# FE.net
KiCad netlist of a schematic drawn in Altium Designer
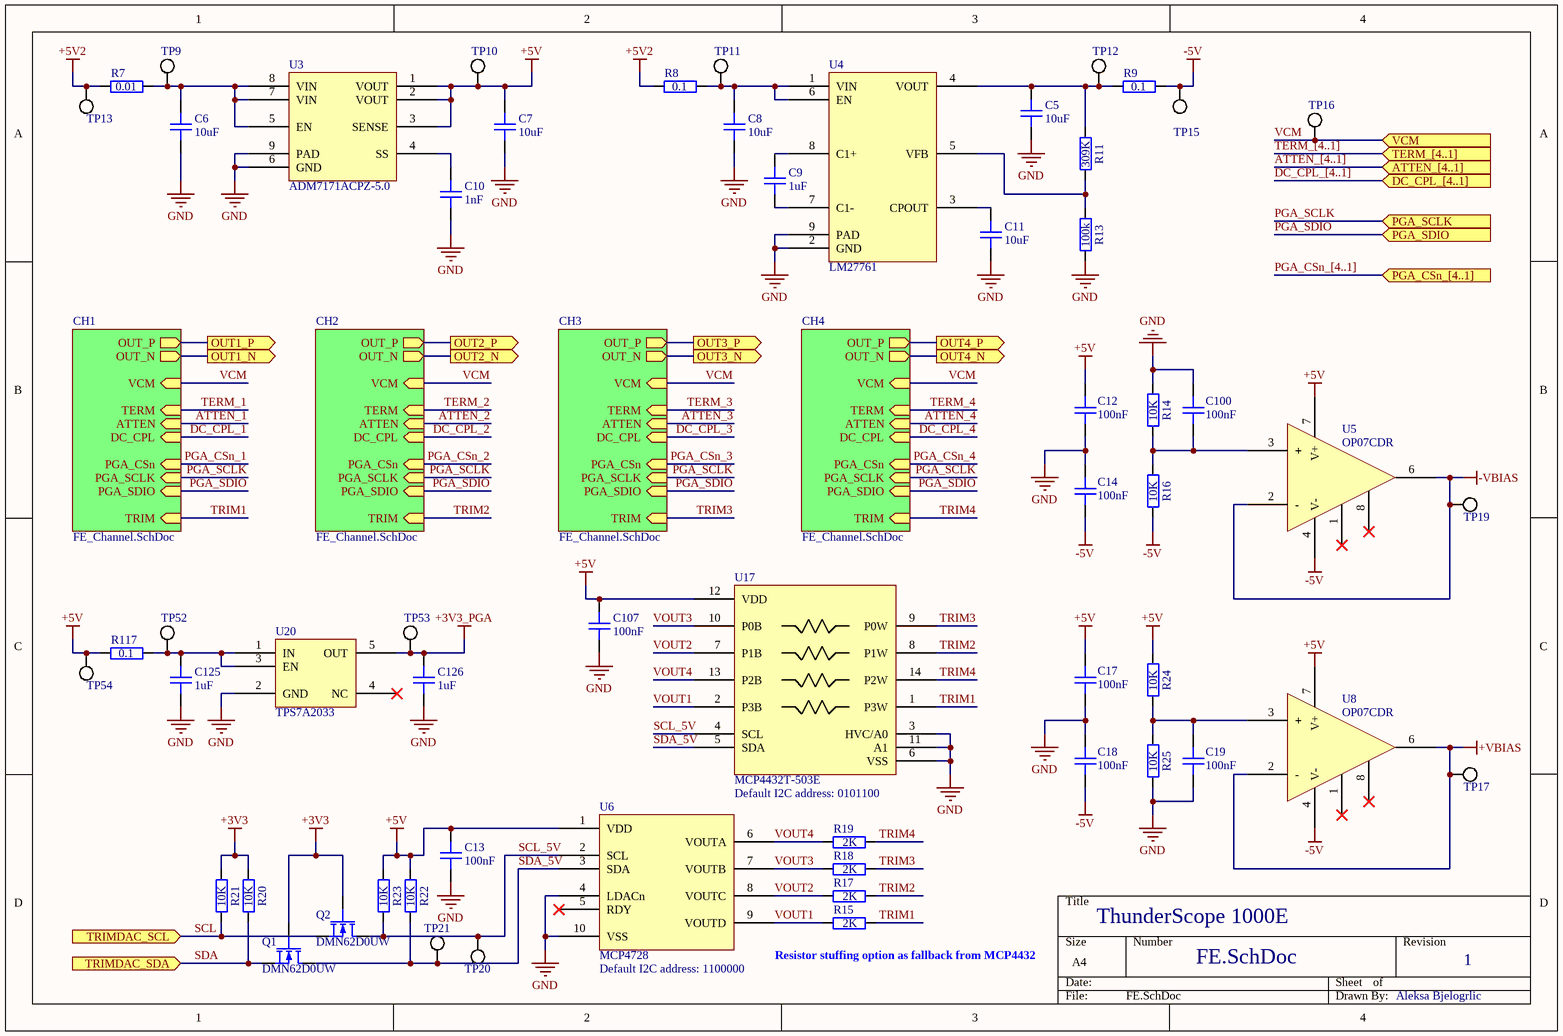
[diagram p0: FE.SchDoc]

(export (version "E")
  (design (tool "Eeschema 10.0.6"))
  (components
    (comp (ref "C5")
      (value "10uF")
      (footprint "GEN_C_0603")
      (libsource (lib "DSO") (part "CAP 10uF 10V X5R 0603"))
    )
    (comp (ref "C6")
      (value "10uF")
      (footprint "GEN_C_0603")
      (libsource (lib "DSO") (part "CAP 10uF 10V X5R 0603"))
    )
    (comp (ref "C7")
      (value "10uF")
      (footprint "GEN_C_0603")
      (libsource (lib "DSO") (part "CAP 10uF 10V X5R 0603"))
    )
    (comp (ref "C8")
      (value "10uF")
      (footprint "GEN_C_0603")
      (libsource (lib "DSO") (part "CAP 10uF 10V X5R 0603"))
    )
    (comp (ref "C9")
      (value "1uF")
      (footprint "GEN_C_0402")
      (libsource (lib "DSO") (part "CAP 1uF 25V X5R 0402"))
    )
    (comp (ref "C10")
      (value "1nF")
      (footprint "GEN_C_0402")
      (libsource (lib "DSO") (part "CAP 1nF 50V C0G 0402"))
    )
    (comp (ref "C11")
      (value "10uF")
      (footprint "GEN_C_0603")
      (libsource (lib "DSO") (part "CAP 10uF 10V X5R 0603"))
    )
    (comp (ref "C12")
      (value "100nF")
      (footprint "GEN_C_0402")
      (libsource (lib "DSO") (part "CAP 100nF 16V X7R 0402"))
    )
    (comp (ref "C13")
      (value "100nF")
      (footprint "GEN_C_0402")
      (libsource (lib "DSO") (part "CAP 100nF 16V X7R 0402"))
    )
    (comp (ref "C14")
      (value "100nF")
      (footprint "GEN_C_0402")
      (libsource (lib "DSO") (part "CAP 100nF 16V X7R 0402"))
    )
    (comp (ref "C17")
      (value "100nF")
      (footprint "GEN_C_0402")
      (libsource (lib "DSO") (part "CAP 100nF 16V X7R 0402"))
    )
    (comp (ref "C18")
      (value "100nF")
      (footprint "GEN_C_0402")
      (libsource (lib "DSO") (part "CAP 100nF 16V X7R 0402"))
    )
    (comp (ref "C19")
      (value "100nF")
      (footprint "GEN_C_0402")
      (libsource (lib "DSO") (part "CAP 100nF 16V X7R 0402"))
    )
    (comp (ref "C100")
      (value "100nF")
      (footprint "GEN_C_0402")
      (libsource (lib "DSO") (part "CAP 100nF 16V X7R 0402"))
    )
    (comp (ref "C107")
      (value "100nF")
      (footprint "GEN_C_0402")
      (libsource (lib "DSO") (part "CAP 100nF 16V X7R 0402"))
    )
    (comp (ref "C125")
      (value "1uF")
      (footprint "GEN_C_0402")
      (libsource (lib "DSO") (part "CAP 1uF 25V X5R 0402"))
    )
    (comp (ref "C126")
      (value "1uF")
      (footprint "GEN_C_0402")
      (libsource (lib "DSO") (part "CAP 1uF 25V X5R 0402"))
    )
    (comp (ref "Q1")
      (value "DMN62D0UW")
      (footprint "GEN_SOT_323")
      (libsource (lib "DSO") (part "NMOS DMN62D0UW"))
    )
    (comp (ref "Q2")
      (value "DMN62D0UW")
      (footprint "GEN_SOT_323")
      (libsource (lib "DSO") (part "NMOS DMN62D0UW"))
    )
    (comp (ref "R7")
      (value "0.01")
      (footprint "GEN_R_0603")
      (fields (field (name "TOLERANCE") "1%"))
      (libsource (lib "DSO") (part "RES 0.01 OHM 1% 1/4W 0603"))
    )
    (comp (ref "R8")
      (value "0.1")
      (footprint "GEN_R_0402")
      (fields (field (name "TOLERANCE") "1%"))
      (libsource (lib "DSO") (part "RES 0.1 OHM 1% 1/6W 0402"))
    )
    (comp (ref "R9")
      (value "0.1")
      (footprint "GEN_R_0402")
      (fields (field (name "TOLERANCE") "1%"))
      (libsource (lib "DSO") (part "RES 0.1 OHM 1% 1/6W 0402"))
    )
    (comp (ref "R11")
      (value "309K")
      (footprint "GEN_R_0402")
      (fields (field (name "TOLERANCE") "1%"))
      (libsource (lib "DSO") (part "RES 309K OHM 1% 1/16W 0402"))
    )
    (comp (ref "R13")
      (value "100k")
      (footprint "GEN_R_0402")
      (fields (field (name "TOLERANCE") "1%"))
      (libsource (lib "DSO") (part "RES 100K OHM 1% 1/10W 0402"))
    )
    (comp (ref "R14")
      (value "10K")
      (footprint "GEN_R_0402")
      (fields (field (name "TOLERANCE") "1%"))
      (libsource (lib "DSO") (part "RES 10K OHM 1% 1/10W 0402"))
    )
    (comp (ref "R15")
      (value "2K")
      (footprint "GEN_R_0402")
      (fields (field (name "TOLERANCE") "1%"))
      (libsource (lib "DSO") (part "RES 2K OHM 1% 1/16W 0402"))
    )
    (comp (ref "R16")
      (value "10K")
      (footprint "GEN_R_0402")
      (fields (field (name "TOLERANCE") "1%"))
      (libsource (lib "DSO") (part "RES 10K OHM 1% 1/10W 0402"))
    )
    (comp (ref "R17")
      (value "2K")
      (footprint "GEN_R_0402")
      (fields (field (name "TOLERANCE") "1%"))
      (libsource (lib "DSO") (part "RES 2K OHM 1% 1/16W 0402"))
    )
    (comp (ref "R18")
      (value "2K")
      (footprint "GEN_R_0402")
      (fields (field (name "TOLERANCE") "1%"))
      (libsource (lib "DSO") (part "RES 2K OHM 1% 1/16W 0402"))
    )
    (comp (ref "R19")
      (value "2K")
      (footprint "GEN_R_0402")
      (fields (field (name "TOLERANCE") "1%"))
      (libsource (lib "DSO") (part "RES 2K OHM 1% 1/16W 0402"))
    )
    (comp (ref "R20")
      (value "10K")
      (footprint "GEN_R_0402")
      (fields (field (name "TOLERANCE") "1%"))
      (libsource (lib "DSO") (part "RES 10K OHM 1% 1/10W 0402"))
    )
    (comp (ref "R21")
      (value "10K")
      (footprint "GEN_R_0402")
      (fields (field (name "TOLERANCE") "1%"))
      (libsource (lib "DSO") (part "RES 10K OHM 1% 1/10W 0402"))
    )
    (comp (ref "R22")
      (value "10K")
      (footprint "GEN_R_0402")
      (fields (field (name "TOLERANCE") "1%"))
      (libsource (lib "DSO") (part "RES 10K OHM 1% 1/10W 0402"))
    )
    (comp (ref "R23")
      (value "10K")
      (footprint "GEN_R_0402")
      (fields (field (name "TOLERANCE") "1%"))
      (libsource (lib "DSO") (part "RES 10K OHM 1% 1/10W 0402"))
    )
    (comp (ref "R24")
      (value "10K")
      (footprint "GEN_R_0402")
      (fields (field (name "TOLERANCE") "1%"))
      (libsource (lib "DSO") (part "RES 10K OHM 1% 1/10W 0402"))
    )
    (comp (ref "R25")
      (value "10K")
      (footprint "GEN_R_0402")
      (fields (field (name "TOLERANCE") "1%"))
      (libsource (lib "DSO") (part "RES 10K OHM 1% 1/10W 0402"))
    )
    (comp (ref "R117")
      (value "0.1")
      (footprint "GEN_R_0402")
      (fields (field (name "TOLERANCE") "1%"))
      (libsource (lib "DSO") (part "RES 0.1 OHM 1% 1/6W 0402"))
    )
    (comp (ref "TP9") (value "PCB") (footprint "GEN_TP_PCB") (libsource (lib "DSO") (part "TP PCB 1mm")))
    (comp (ref "TP10") (value "PCB") (footprint "GEN_TP_PCB") (libsource (lib "DSO") (part "TP PCB 1mm")))
    (comp (ref "TP11") (value "PCB") (footprint "GEN_TP_PCB") (libsource (lib "DSO") (part "TP PCB 1mm")))
    (comp (ref "TP12") (value "PCB") (footprint "GEN_TP_PCB") (libsource (lib "DSO") (part "TP PCB 1mm")))
    (comp (ref "TP13") (value "PCB") (footprint "GEN_TP_PCB") (libsource (lib "DSO") (part "TP PCB 1mm")))
    (comp (ref "TP15") (value "PCB") (footprint "GEN_TP_PCB") (libsource (lib "DSO") (part "TP PCB 1mm")))
    (comp (ref "TP16") (value "PCB") (footprint "GEN_TP_PCB") (libsource (lib "DSO") (part "TP PCB 1mm")))
    (comp (ref "TP17") (value "PCB") (footprint "GEN_TP_PCB") (libsource (lib "DSO") (part "TP PCB 1mm")))
    (comp (ref "TP19") (value "PCB") (footprint "GEN_TP_PCB") (libsource (lib "DSO") (part "TP PCB 1mm")))
    (comp (ref "TP20") (value "PCB") (footprint "GEN_TP_PCB") (libsource (lib "DSO") (part "TP PCB 1mm")))
    (comp (ref "TP21") (value "PCB") (footprint "GEN_TP_PCB") (libsource (lib "DSO") (part "TP PCB 1mm")))
    (comp (ref "TP52") (value "PCB") (footprint "GEN_TP_PCB") (libsource (lib "DSO") (part "TP PCB 1mm")))
    (comp (ref "TP53") (value "PCB") (footprint "GEN_TP_PCB") (libsource (lib "DSO") (part "TP PCB 1mm")))
    (comp (ref "TP54") (value "PCB") (footprint "GEN_TP_PCB") (libsource (lib "DSO") (part "TP PCB 1mm")))
    (comp (ref "U3")
      (value "ADM7171ACPZ-5.0")
      (footprint "AD_DFN8_CP-8-21")
      (libsource (lib "DSO") (part "IC LDO ADM7171ACPZ-5.0"))
    )
    (comp (ref "U4")
      (value "LM27761")
      (footprint "TI_WSON8_DSG0008A")
      (libsource (lib "DSO") (part "IC CPUMP LM27761"))
    )
    (comp (ref "U5")
      (value "OP07CDR")
      (footprint "TI_SOIC8_D0008A")
      (libsource (lib "DSO") (part "IC OPAMP OP07CDR"))
    )
    (comp (ref "U6")
      (value "MCP4728")
      (footprint "MC_MSOP10_UN")
      (libsource (lib "DSO") (part "IC DAC QUAD MCP4728"))
    )
    (comp (ref "U8")
      (value "OP07CDR")
      (footprint "TI_SOIC8_D0008A")
      (libsource (lib "DSO") (part "IC OPAMP OP07CDR"))
    )
    (comp (ref "U17")
      (value "MCP4432T-503E")
      (footprint "MC_TSSOP14")
      (libsource (lib "DSO") (part "IC DIGIPOT QUAD MCP4432T-503E"))
    )
    (comp (ref "U20")
      (value "TPS7A2033")
      (footprint "GEN_SOT23_5_950_2900X1600X1450")
      (fields
        (field (name "MANUFACTURER") "Texas Instruments")
        (field (name "MANUFACTURER PART NUMBER") "TPS7A2033PDBVR")
      )
      (libsource (lib "DSO") (part "IC LDO TPS7A2033"))
    )
  )
  (nets
    (net (code "1") (name "+3V3") (class "Default")
      (node (ref "Q1") (pin "2") (pinfunction "G_2") (pintype "passive"))
      (node (ref "Q2") (pin "2") (pinfunction "G_2") (pintype "passive"))
      (node (ref "R20") (pin "2") (pinfunction "2_2") (pintype "passive"))
      (node (ref "R21") (pin "2") (pinfunction "2_2") (pintype "passive"))
    )
    (net (code "2") (name "+3V3_PGA") (class "Default")
      (node (ref "C126") (pin "2") (pinfunction "2_2") (pintype "passive"))
      (node (ref "TP53") (pin "1") (pinfunction "1_1") (pintype "passive"))
      (node (ref "U20") (pin "5") (pinfunction "OUT_5") (pintype "power_in"))
    )
    (net (code "3") (name "+5V") (class "Default")
      (node (ref "C107") (pin "2") (pinfunction "2_2") (pintype "passive"))
      (node (ref "C12") (pin "1") (pinfunction "1_1") (pintype "passive"))
      (node (ref "C13") (pin "2") (pinfunction "2_2") (pintype "passive"))
      (node (ref "C17") (pin "1") (pinfunction "1_1") (pintype "passive"))
      (node (ref "C7") (pin "2") (pinfunction "2_2") (pintype "passive"))
      (node (ref "R117") (pin "1") (pinfunction "1_1") (pintype "passive"))
      (node (ref "R22") (pin "2") (pinfunction "2_2") (pintype "passive"))
      (node (ref "R23") (pin "2") (pinfunction "2_2") (pintype "passive"))
      (node (ref "R24") (pin "2") (pinfunction "2_2") (pintype "passive"))
      (node (ref "TP10") (pin "1") (pinfunction "1_1") (pintype "passive"))
      (node (ref "TP54") (pin "1") (pinfunction "1_1") (pintype "passive"))
      (node (ref "U17") (pin "12") (pinfunction "VDD_12") (pintype "power_in"))
      (node (ref "U3") (pin "1") (pinfunction "VOUT_1") (pintype "power_in"))
      (node (ref "U3") (pin "2") (pinfunction "VOUT_2") (pintype "power_in"))
      (node (ref "U3") (pin "3") (pinfunction "SENSE_3") (pintype "passive"))
      (node (ref "U5") (pin "7") (pinfunction "V+_7") (pintype "passive"))
      (node (ref "U6") (pin "1") (pinfunction "VDD_1") (pintype "power_in"))
      (node (ref "U8") (pin "7") (pinfunction "V+_7") (pintype "passive"))
    )
    (net (code "4") (name "+5V2") (class "Default")
      (node (ref "R7") (pin "1") (pinfunction "1_1") (pintype "passive"))
      (node (ref "R8") (pin "1") (pinfunction "1_1") (pintype "passive"))
      (node (ref "TP13") (pin "1") (pinfunction "1_1") (pintype "passive"))
    )
    (net (code "5") (name "+VBIAS") (class "Default")
      (node (ref "TP17") (pin "1") (pinfunction "1_1") (pintype "passive"))
      (node (ref "U8") (pin "2") (pinfunction "-_2") (pintype "passive"))
      (node (ref "U8") (pin "6") (pinfunction "OUT_6") (pintype "passive"))
    )
    (net (code "6") (name "-5V") (class "Default")
      (node (ref "C14") (pin "2") (pinfunction "2_2") (pintype "passive"))
      (node (ref "C18") (pin "2") (pinfunction "2_2") (pintype "passive"))
      (node (ref "R16") (pin "1") (pinfunction "1_1") (pintype "passive"))
      (node (ref "R9") (pin "2") (pinfunction "2_2") (pintype "passive"))
      (node (ref "TP15") (pin "1") (pinfunction "1_1") (pintype "passive"))
      (node (ref "U5") (pin "4") (pinfunction "V-_4") (pintype "passive"))
      (node (ref "U8") (pin "4") (pinfunction "V-_4") (pintype "passive"))
    )
    (net (code "7") (name "-VBIAS") (class "Default")
      (node (ref "TP19") (pin "1") (pinfunction "1_1") (pintype "passive"))
      (node (ref "U5") (pin "2") (pinfunction "-_2") (pintype "passive"))
      (node (ref "U5") (pin "6") (pinfunction "OUT_6") (pintype "passive"))
    )
    (net (code "33") (name "/SCL") (class "Default")
      (node (ref "Q2") (pin "3") (pinfunction "S_3") (pintype "passive"))
      (node (ref "R21") (pin "1") (pinfunction "1_1") (pintype "passive"))
    )
    (net (code "34") (name "/SCL_5V") (class "Default")
      (node (ref "Q2") (pin "1") (pinfunction "D_1") (pintype "passive"))
      (node (ref "R23") (pin "1") (pinfunction "1_1") (pintype "passive"))
      (node (ref "TP20") (pin "1") (pinfunction "1_1") (pintype "passive"))
      (node (ref "U17") (pin "4") (pinfunction "SCL_4") (pintype "passive"))
      (node (ref "U6") (pin "2") (pinfunction "SCL_2") (pintype "passive"))
    )
    (net (code "35") (name "/SDA") (class "Default")
      (node (ref "Q1") (pin "3") (pinfunction "S_3") (pintype "passive"))
      (node (ref "R20") (pin "1") (pinfunction "1_1") (pintype "passive"))
    )
    (net (code "36") (name "/SDA_5V") (class "Default")
      (node (ref "Q1") (pin "1") (pinfunction "D_1") (pintype "passive"))
      (node (ref "R22") (pin "1") (pinfunction "1_1") (pintype "passive"))
      (node (ref "TP21") (pin "1") (pinfunction "1_1") (pintype "passive"))
      (node (ref "U17") (pin "5") (pinfunction "SDA_5") (pintype "passive"))
      (node (ref "U6") (pin "3") (pinfunction "SDA_3") (pintype "passive"))
    )
    (net (code "42") (name "/TRIM1") (class "Default")
      (node (ref "R15") (pin "1") (pinfunction "1_1") (pintype "passive"))
      (node (ref "U17") (pin "1") (pinfunction "P3W_1") (pintype "passive"))
    )
    (net (code "43") (name "/TRIM2") (class "Default")
      (node (ref "R17") (pin "1") (pinfunction "1_1") (pintype "passive"))
      (node (ref "U17") (pin "8") (pinfunction "P1W_8") (pintype "passive"))
    )
    (net (code "44") (name "/TRIM3") (class "Default")
      (node (ref "R18") (pin "1") (pinfunction "1_1") (pintype "passive"))
      (node (ref "U17") (pin "9") (pinfunction "P0W_9") (pintype "passive"))
    )
    (net (code "45") (name "/TRIM4") (class "Default")
      (node (ref "R19") (pin "1") (pinfunction "1_1") (pintype "passive"))
      (node (ref "U17") (pin "14") (pinfunction "P2W_14") (pintype "passive"))
    )
    (net (code "46") (name "/VCM") (class "Default")
      (node (ref "TP16") (pin "1") (pinfunction "1_1") (pintype "passive"))
    )
    (net (code "47") (name "/VOUT1") (class "Default")
      (node (ref "R15") (pin "2") (pinfunction "2_2") (pintype "passive"))
      (node (ref "U17") (pin "2") (pinfunction "P3B_2") (pintype "passive"))
      (node (ref "U6") (pin "9") (pinfunction "VOUTD_9") (pintype "passive"))
    )
    (net (code "48") (name "/VOUT2") (class "Default")
      (node (ref "R17") (pin "2") (pinfunction "2_2") (pintype "passive"))
      (node (ref "U17") (pin "7") (pinfunction "P1B_7") (pintype "passive"))
      (node (ref "U6") (pin "8") (pinfunction "VOUTC_8") (pintype "passive"))
    )
    (net (code "49") (name "/VOUT3") (class "Default")
      (node (ref "R18") (pin "2") (pinfunction "2_2") (pintype "passive"))
      (node (ref "U17") (pin "10") (pinfunction "P0B_10") (pintype "passive"))
      (node (ref "U6") (pin "7") (pinfunction "VOUTB_7") (pintype "passive"))
    )
    (net (code "50") (name "/VOUT4") (class "Default")
      (node (ref "R19") (pin "2") (pinfunction "2_2") (pintype "passive"))
      (node (ref "U17") (pin "13") (pinfunction "P2B_13") (pintype "passive"))
      (node (ref "U6") (pin "6") (pinfunction "VOUTA_6") (pintype "passive"))
    )
    (net (code "51") (name "GND") (class "Default")
      (node (ref "C10") (pin "1") (pinfunction "1_1") (pintype "passive"))
      (node (ref "C100") (pin "1") (pinfunction "1_1") (pintype "passive"))
      (node (ref "C107") (pin "1") (pinfunction "1_1") (pintype "passive"))
      (node (ref "C11") (pin "1") (pinfunction "1_1") (pintype "passive"))
      (node (ref "C12") (pin "2") (pinfunction "2_2") (pintype "passive"))
      (node (ref "C125") (pin "1") (pinfunction "1_1") (pintype "passive"))
      (node (ref "C126") (pin "1") (pinfunction "1_1") (pintype "passive"))
      (node (ref "C13") (pin "1") (pinfunction "1_1") (pintype "passive"))
      (node (ref "C14") (pin "1") (pinfunction "1_1") (pintype "passive"))
      (node (ref "C17") (pin "2") (pinfunction "2_2") (pintype "passive"))
      (node (ref "C18") (pin "1") (pinfunction "1_1") (pintype "passive"))
      (node (ref "C19") (pin "1") (pinfunction "1_1") (pintype "passive"))
      (node (ref "C5") (pin "1") (pinfunction "1_1") (pintype "passive"))
      (node (ref "C6") (pin "1") (pinfunction "1_1") (pintype "passive"))
      (node (ref "C7") (pin "1") (pinfunction "1_1") (pintype "passive"))
      (node (ref "C8") (pin "1") (pinfunction "1_1") (pintype "passive"))
      (node (ref "R13") (pin "1") (pinfunction "1_1") (pintype "passive"))
      (node (ref "R14") (pin "2") (pinfunction "2_2") (pintype "passive"))
      (node (ref "R25") (pin "1") (pinfunction "1_1") (pintype "passive"))
      (node (ref "U17") (pin "11") (pinfunction "A1_11") (pintype "passive"))
      (node (ref "U17") (pin "3") (pinfunction "HVC/A0_3") (pintype "passive"))
      (node (ref "U17") (pin "6") (pinfunction "VSS_6") (pintype "power_in"))
      (node (ref "U20") (pin "2") (pinfunction "GND_2") (pintype "power_in"))
      (node (ref "U3") (pin "6") (pinfunction "GND_6") (pintype "power_in"))
      (node (ref "U3") (pin "9") (pinfunction "PAD_9") (pintype "passive"))
      (node (ref "U4") (pin "2") (pinfunction "GND_2") (pintype "power_in"))
      (node (ref "U4") (pin "9") (pinfunction "PAD_9") (pintype "power_in"))
      (node (ref "U6") (pin "10") (pinfunction "VSS_10") (pintype "power_in"))
      (node (ref "U6") (pin "4") (pinfunction "LDACn_4") (pintype "passive"))
    )
    (net (code "52") (name "Net-(U3-EN)") (class "Default")
      (node (ref "C6") (pin "2") (pinfunction "2_2") (pintype "passive"))
      (node (ref "R7") (pin "2") (pinfunction "2_2") (pintype "passive"))
      (node (ref "TP9") (pin "1") (pinfunction "1_1") (pintype "passive"))
      (node (ref "U3") (pin "5") (pinfunction "EN_5") (pintype "passive"))
      (node (ref "U3") (pin "7") (pinfunction "VIN_7") (pintype "power_in"))
      (node (ref "U3") (pin "8") (pinfunction "VIN_8") (pintype "power_in"))
    )
    (net (code "53") (name "Net-(U3-SS)") (class "Default")
      (node (ref "C10") (pin "2") (pinfunction "2_2") (pintype "passive"))
      (node (ref "U3") (pin "4") (pinfunction "SS_4") (pintype "passive"))
    )
    (net (code "54") (name "Net-(U4-C1+)") (class "Default")
      (node (ref "C9") (pin "2") (pinfunction "2_2") (pintype "passive"))
      (node (ref "U4") (pin "8") (pinfunction "C1+_8") (pintype "passive"))
    )
    (net (code "55") (name "Net-(U4-C1-)") (class "Default")
      (node (ref "C9") (pin "1") (pinfunction "1_1") (pintype "passive"))
      (node (ref "U4") (pin "7") (pinfunction "C1-_7") (pintype "passive"))
    )
    (net (code "56") (name "Net-(U4-CPOUT)") (class "Default")
      (node (ref "C11") (pin "2") (pinfunction "2_2") (pintype "passive"))
      (node (ref "U4") (pin "3") (pinfunction "CPOUT_3") (pintype "passive"))
    )
    (net (code "57") (name "Net-(U4-EN)") (class "Default")
      (node (ref "C8") (pin "2") (pinfunction "2_2") (pintype "passive"))
      (node (ref "R8") (pin "2") (pinfunction "2_2") (pintype "passive"))
      (node (ref "TP11") (pin "1") (pinfunction "1_1") (pintype "passive"))
      (node (ref "U4") (pin "1") (pinfunction "VIN_1") (pintype "power_in"))
      (node (ref "U4") (pin "6") (pinfunction "EN_6") (pintype "passive"))
    )
    (net (code "58") (name "Net-(U4-VFB)") (class "Default")
      (node (ref "R11") (pin "1") (pinfunction "1_1") (pintype "passive"))
      (node (ref "R13") (pin "2") (pinfunction "2_2") (pintype "passive"))
      (node (ref "U4") (pin "5") (pinfunction "VFB_5") (pintype "passive"))
    )
    (net (code "59") (name "Net-(U4-VOUT)") (class "Default")
      (node (ref "C5") (pin "2") (pinfunction "2_2") (pintype "passive"))
      (node (ref "R11") (pin "2") (pinfunction "2_2") (pintype "passive"))
      (node (ref "R9") (pin "1") (pinfunction "1_1") (pintype "passive"))
      (node (ref "TP12") (pin "1") (pinfunction "1_1") (pintype "passive"))
      (node (ref "U4") (pin "4") (pinfunction "VOUT_4") (pintype "power_in"))
    )
    (net (code "60") (name "Net-(U5-+)") (class "Default")
      (node (ref "C100") (pin "2") (pinfunction "2_2") (pintype "passive"))
      (node (ref "R14") (pin "1") (pinfunction "1_1") (pintype "passive"))
      (node (ref "R16") (pin "2") (pinfunction "2_2") (pintype "passive"))
      (node (ref "U5") (pin "3") (pinfunction "+_3") (pintype "passive"))
    )
    (net (code "61") (name "Net-(U8-+)") (class "Default")
      (node (ref "C19") (pin "2") (pinfunction "2_2") (pintype "passive"))
      (node (ref "R24") (pin "1") (pinfunction "1_1") (pintype "passive"))
      (node (ref "R25") (pin "2") (pinfunction "2_2") (pintype "passive"))
      (node (ref "U8") (pin "3") (pinfunction "+_3") (pintype "passive"))
    )
    (net (code "62") (name "Net-(U20-EN)") (class "Default")
      (node (ref "C125") (pin "2") (pinfunction "2_2") (pintype "passive"))
      (node (ref "R117") (pin "2") (pinfunction "2_2") (pintype "passive"))
      (node (ref "TP52") (pin "1") (pinfunction "1_1") (pintype "passive"))
      (node (ref "U20") (pin "1") (pinfunction "IN_1") (pintype "power_in"))
      (node (ref "U20") (pin "3") (pinfunction "EN_3") (pintype "passive"))
    )
    (net (code "63") (name "unconnected-(U5-N1-Pad1)") (class "Default")
      (node (ref "U5") (pin "1") (pinfunction "N1_1") (pintype "passive+no_connect"))
    )
    (net (code "64") (name "unconnected-(U5-N2-Pad8)") (class "Default")
      (node (ref "U5") (pin "8") (pinfunction "N2_8") (pintype "passive+no_connect"))
    )
    (net (code "65") (name "unconnected-(U6-RDY-Pad5)") (class "Default")
      (node (ref "U6") (pin "5") (pinfunction "RDY_5") (pintype "passive+no_connect"))
    )
    (net (code "66") (name "unconnected-(U8-N1-Pad1)") (class "Default")
      (node (ref "U8") (pin "1") (pinfunction "N1_1") (pintype "passive+no_connect"))
    )
    (net (code "67") (name "unconnected-(U8-N2-Pad8)") (class "Default")
      (node (ref "U8") (pin "8") (pinfunction "N2_8") (pintype "passive+no_connect"))
    )
    (net (code "68") (name "unconnected-(U20-NC-Pad4)") (class "Default")
      (node (ref "U20") (pin "4") (pinfunction "NC_4") (pintype "passive+no_connect"))
    )
  )
)
